# SCH_Pico_funboard_core2_2025-12-29.net
KiCad netlist of a schematic drawn in EasyEDA
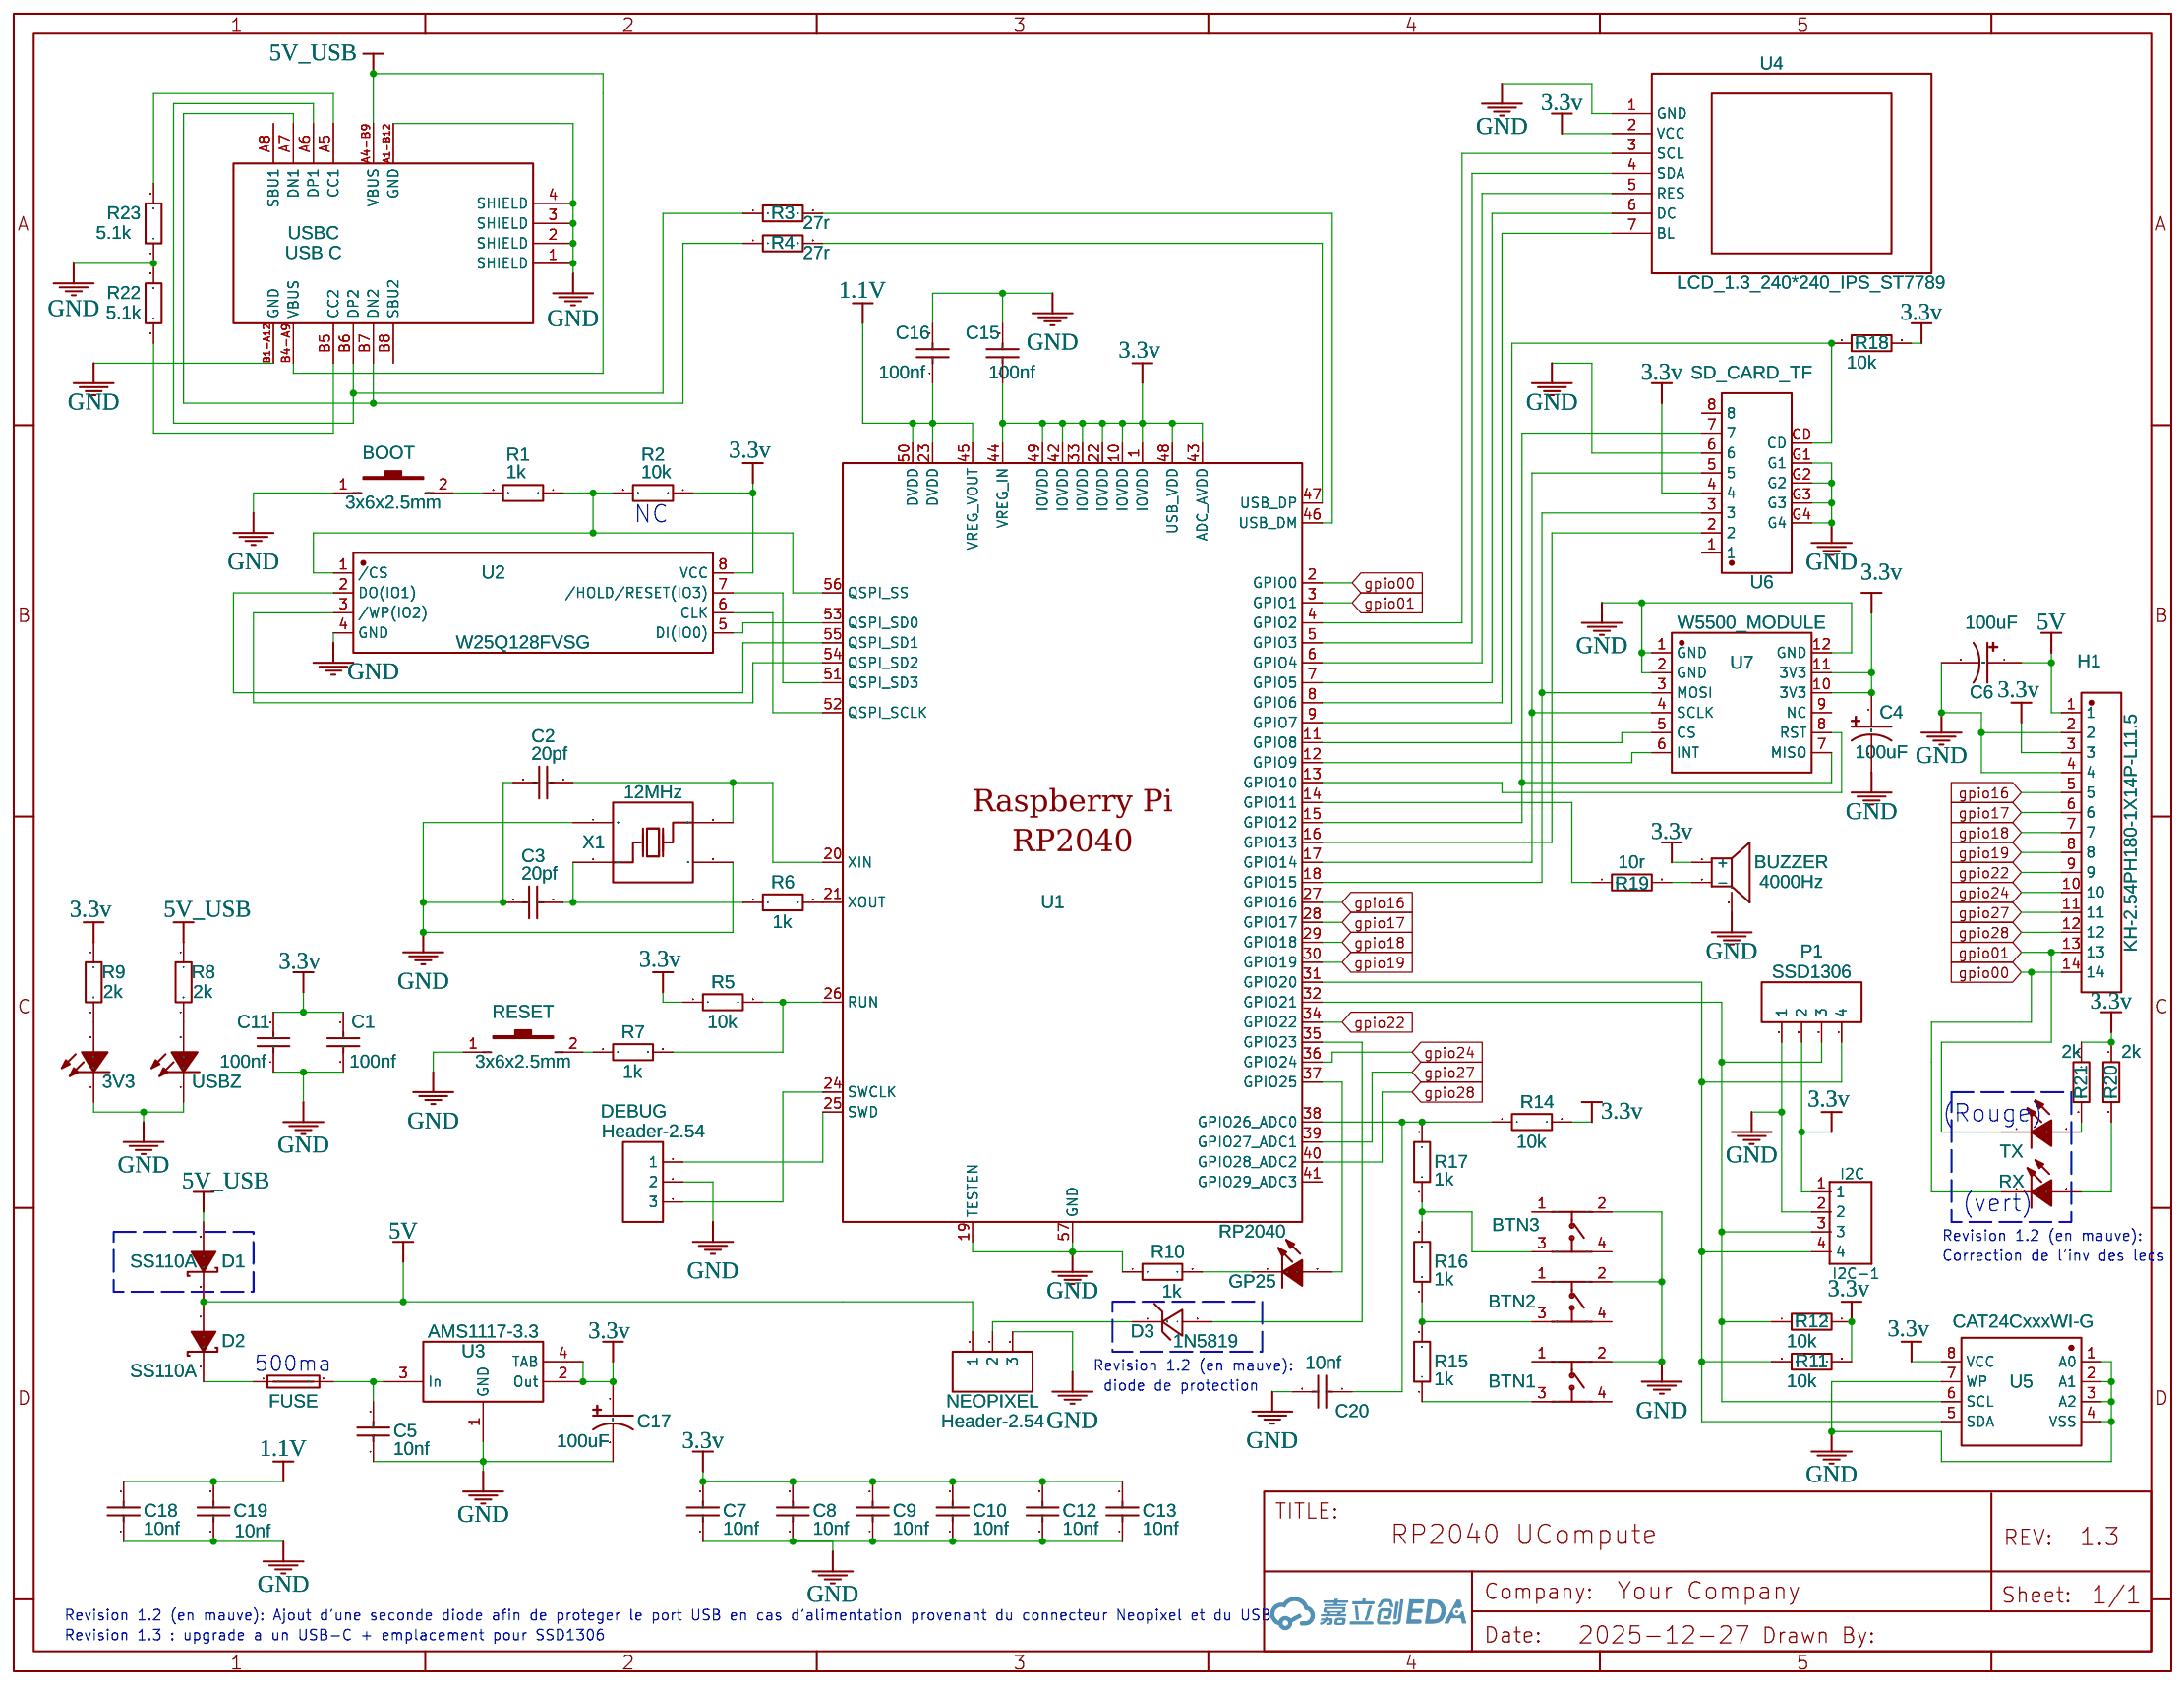
[diagram p0: schematic sheet]

(export (version "E")
  (design (tool "Eeschema 10.0.6"))
  (components
    (comp (ref "3V3")
      (value "XL-1206QPC")
      (fields (field (name "Manufacturer") "LCSC"))
      (libsource (lib "") (part "XL-1206QPC"))
    )
    (comp (ref "BOOT")
      (value "3x6x2.5mm")
      (fields (field (name "Manufacturer") "ReliaPro"))
      (libsource (lib "") (part "3x6x2.5mm"))
    )
    (comp (ref "BTN1")
      (value "TC-1102-A-J-R")
      (fields (field (name "Manufacturer") "XKB Connectivity(中国星坤)"))
      (libsource (lib "") (part "TC-1102-A-J-R"))
    )
    (comp (ref "BTN2")
      (value "TC-1102-A-J-R")
      (fields (field (name "Manufacturer") "XKB Connectivity(中国星坤)"))
      (libsource (lib "") (part "TC-1102-A-J-R"))
    )
    (comp (ref "BTN3")
      (value "TC-1102-A-J-R")
      (fields (field (name "Manufacturer") "XKB Connectivity(中国星坤)"))
      (libsource (lib "") (part "TC-1102-A-J-R"))
    )
    (comp (ref "BUZZER")
      (value "4000Hz")
      (fields (field (name "Manufacturer Part") "MLT-5030") (field (name "Manufacturer") "华能"))
      (libsource (lib "") (part "MLT-5030"))
    )
    (comp (ref "C1")
      (value "100nf")
      (fields (field (name "Manufacturer Part") "0805CG220J500NT") (field (name "Manufacturer") "FH"))
      (libsource (lib "") (part "0805CG220J500NT_3"))
    )
    (comp (ref "C2")
      (value "20pf")
      (fields (field (name "Manufacturer Part") "0805CG220J500NT") (field (name "Manufacturer") "FH"))
      (libsource (lib "") (part "0805CG220J500NT"))
    )
    (comp (ref "C3")
      (value "20pf")
      (fields (field (name "Manufacturer Part") "0805CG220J500NT") (field (name "Manufacturer") "FH"))
      (libsource (lib "") (part "0805CG220J500NT"))
    )
    (comp (ref "C4")
      (value "100uF")
      (fields
        (field (name "Manufacturer Part") "TLJA107M010R1400")
        (field (name "Manufacturer") "Kyocera AVX")
      )
      (libsource (lib "") (part "TLJA107M010R1400"))
    )
    (comp (ref "C5")
      (value "10nf")
      (fields (field (name "Manufacturer Part") "0805CG220J500NT") (field (name "Manufacturer") "FH"))
      (libsource (lib "") (part "0805CG220J500NT_1"))
    )
    (comp (ref "C6")
      (value "100uF")
      (fields
        (field (name "Manufacturer Part") "TLJA107M010R1400")
        (field (name "Manufacturer") "Kyocera AVX")
      )
      (libsource (lib "") (part "TLJA107M010R1400_1"))
    )
    (comp (ref "C7")
      (value "10nf")
      (fields (field (name "Manufacturer Part") "0805CG220J500NT") (field (name "Manufacturer") "FH"))
      (libsource (lib "") (part "0805CG220J500NT_1"))
    )
    (comp (ref "C8")
      (value "10nf")
      (fields (field (name "Manufacturer Part") "0805CG220J500NT") (field (name "Manufacturer") "FH"))
      (libsource (lib "") (part "0805CG220J500NT_1"))
    )
    (comp (ref "C9")
      (value "10nf")
      (fields (field (name "Manufacturer Part") "0805CG220J500NT") (field (name "Manufacturer") "FH"))
      (libsource (lib "") (part "0805CG220J500NT_1"))
    )
    (comp (ref "C10")
      (value "10nf")
      (fields (field (name "Manufacturer Part") "0805CG220J500NT") (field (name "Manufacturer") "FH"))
      (libsource (lib "") (part "0805CG220J500NT_1"))
    )
    (comp (ref "C11")
      (value "100nf")
      (fields (field (name "Manufacturer Part") "0805CG220J500NT") (field (name "Manufacturer") "FH"))
      (libsource (lib "") (part "0805CG220J500NT_1"))
    )
    (comp (ref "C12")
      (value "10nf")
      (fields (field (name "Manufacturer Part") "0805CG220J500NT") (field (name "Manufacturer") "FH"))
      (libsource (lib "") (part "0805CG220J500NT_1"))
    )
    (comp (ref "C13")
      (value "10nf")
      (fields (field (name "Manufacturer Part") "0805CG220J500NT") (field (name "Manufacturer") "FH"))
      (libsource (lib "") (part "0805CG220J500NT_1"))
    )
    (comp (ref "C15")
      (value "100nf")
      (fields (field (name "Manufacturer Part") "0805CG220J500NT") (field (name "Manufacturer") "FH"))
      (libsource (lib "") (part "0805CG220J500NT_1"))
    )
    (comp (ref "C16")
      (value "100nf")
      (fields (field (name "Manufacturer Part") "0805CG220J500NT") (field (name "Manufacturer") "FH"))
      (libsource (lib "") (part "0805CG220J500NT_1"))
    )
    (comp (ref "C17")
      (value "100uF")
      (fields
        (field (name "Manufacturer Part") "TLJA107M010R1400")
        (field (name "Manufacturer") "Kyocera AVX")
      )
      (libsource (lib "") (part "TLJA107M010R1400_2"))
    )
    (comp (ref "C18")
      (value "10nf")
      (fields (field (name "Manufacturer Part") "0805CG220J500NT") (field (name "Manufacturer") "FH"))
      (libsource (lib "") (part "0805CG220J500NT_1"))
    )
    (comp (ref "C19")
      (value "10nf")
      (fields (field (name "Manufacturer Part") "0805CG220J500NT") (field (name "Manufacturer") "FH"))
      (libsource (lib "") (part "0805CG220J500NT_1"))
    )
    (comp (ref "C20")
      (value "10nf")
      (fields (field (name "Manufacturer Part") "0805CG220J500NT") (field (name "Manufacturer") "FH"))
      (libsource (lib "") (part "0805CG220J500NT_2"))
    )
    (comp (ref "D1")
      (value "SS110A")
      (fields (field (name "Manufacturer") "Yangzhou Yangjie Elec Tech"))
      (libsource (lib "") (part "SS110A"))
    )
    (comp (ref "D2")
      (value "SS110A")
      (fields (field (name "Manufacturer") "Yangzhou Yangjie Elec Tech"))
      (libsource (lib "") (part "SS110A"))
    )
    (comp (ref "D3")
      (value "1N5819")
      (fields (field (name "Manufacturer Part") "1N4148D"))
      (libsource (lib "") (part "1N4148D"))
    )
    (comp (ref "DEBUG")
      (value "Header-2.54")
      (fields (field (name "Manufacturer Part") "2.54-1*3P针") (field (name "Manufacturer") "BOOMELE(博穆精密)"))
      (libsource (lib "") (part "Header-Male-2.54_1x3"))
    )
    (comp (ref "FUSE")
      (value "FUSE1206")
      (fields (field (name "Manufacturer Part") "D22051903536_fuse1206"))
      (libsource (lib "") (part "D22051903536_FUSE1206"))
    )
    (comp (ref "GP25")
      (value "XL-1206QPC")
      (fields (field (name "Manufacturer") "LCSC"))
      (libsource (lib "") (part "XL-1206QPC_4"))
    )
    (comp (ref "H1")
      (value "KH-2.54PH180-1X14P-L11.5")
      (fields (field (name "Manufacturer") "kinghelm(金航标)"))
      (libsource (lib "") (part "KH-2.54PH180-1X14P-L11.5"))
    )
    (comp (ref "I2C-1") (value "I2C") (libsource (lib "") (part "Unknown_921_-225")))
    (comp (ref "NEOPIXEL")
      (value "Header-2.54")
      (fields (field (name "Manufacturer Part") "2.54-1*3P针") (field (name "Manufacturer") "BOOMELE(博穆精密)"))
      (libsource (lib "") (part "Header-Male-2.54_1x3_1"))
    )
    (comp (ref "P1")
      (value "SSD1306")
      (fields
        (field (name "Manufacturer Part") "Header-Female-2.54_1x4")
        (field (name "Manufacturer") "ReliaPro")
      )
      (libsource (lib "") (part "Header-Female-2.54_1x4"))
    )
    (comp (ref "R1")
      (value "1k")
      (fields (field (name "Manufacturer Part") "RC0805DR-071KL") (field (name "Manufacturer") "YAGEO(国巨)"))
      (libsource (lib "") (part "RC0805DR-071KL_3"))
    )
    (comp (ref "R2")
      (value "10k")
      (fields (field (name "Manufacturer Part") "RC0805DR-071KL") (field (name "Manufacturer") "YAGEO(国巨)"))
      (libsource (lib "") (part "RC0805DR-071KL_3"))
    )
    (comp (ref "R3")
      (value "27r")
      (fields (field (name "Manufacturer Part") "RC0805DR-071KL") (field (name "Manufacturer") "YAGEO(国巨)"))
      (libsource (lib "") (part "RC0805DR-071KL"))
    )
    (comp (ref "R4")
      (value "27r")
      (fields (field (name "Manufacturer Part") "RC0805DR-071KL") (field (name "Manufacturer") "YAGEO(国巨)"))
      (libsource (lib "") (part "RC0805DR-071KL"))
    )
    (comp (ref "R5")
      (value "10k")
      (fields (field (name "Manufacturer Part") "RC0805DR-071KL") (field (name "Manufacturer") "YAGEO(国巨)"))
      (libsource (lib "") (part "RC0805DR-071KL"))
    )
    (comp (ref "R6")
      (value "1k")
      (fields (field (name "Manufacturer Part") "RC0805DR-071KL") (field (name "Manufacturer") "YAGEO(国巨)"))
      (libsource (lib "") (part "RC0805DR-071KL"))
    )
    (comp (ref "R7")
      (value "1k")
      (fields (field (name "Manufacturer Part") "RC0805DR-071KL") (field (name "Manufacturer") "YAGEO(国巨)"))
      (libsource (lib "") (part "RC0805DR-071KL"))
    )
    (comp (ref "R8")
      (value "2k")
      (fields (field (name "Manufacturer Part") "RC0805DR-071KL") (field (name "Manufacturer") "YAGEO(国巨)"))
      (libsource (lib "") (part "RC0805DR-071KL_1"))
    )
    (comp (ref "R9")
      (value "2k")
      (fields (field (name "Manufacturer Part") "RC0805DR-071KL") (field (name "Manufacturer") "YAGEO(国巨)"))
      (libsource (lib "") (part "RC0805DR-071KL_1"))
    )
    (comp (ref "R10")
      (value "1k")
      (fields (field (name "Manufacturer Part") "RC0805DR-071KL") (field (name "Manufacturer") "YAGEO(国巨)"))
      (libsource (lib "") (part "RC0805DR-071KL"))
    )
    (comp (ref "R11")
      (value "10k")
      (fields (field (name "Manufacturer Part") "RC0805DR-071KL") (field (name "Manufacturer") "YAGEO(国巨)"))
      (libsource (lib "") (part "RC0805DR-071KL"))
    )
    (comp (ref "R12")
      (value "10k")
      (fields (field (name "Manufacturer Part") "RC0805DR-071KL") (field (name "Manufacturer") "YAGEO(国巨)"))
      (libsource (lib "") (part "RC0805DR-071KL"))
    )
    (comp (ref "R14")
      (value "10k")
      (fields (field (name "Manufacturer Part") "RC0805DR-071KL") (field (name "Manufacturer") "YAGEO(国巨)"))
      (libsource (lib "") (part "RC0805DR-071KL"))
    )
    (comp (ref "R15")
      (value "1k")
      (fields (field (name "Manufacturer Part") "RC0805DR-071KL") (field (name "Manufacturer") "YAGEO(国巨)"))
      (libsource (lib "") (part "RC0805DR-071KL_2"))
    )
    (comp (ref "R16")
      (value "1k")
      (fields (field (name "Manufacturer Part") "RC0805DR-071KL") (field (name "Manufacturer") "YAGEO(国巨)"))
      (libsource (lib "") (part "RC0805DR-071KL_2"))
    )
    (comp (ref "R17")
      (value "1k")
      (fields (field (name "Manufacturer Part") "RC0805DR-071KL") (field (name "Manufacturer") "YAGEO(国巨)"))
      (libsource (lib "") (part "RC0805DR-071KL_2"))
    )
    (comp (ref "R18")
      (value "10k")
      (fields (field (name "Manufacturer Part") "RC0805DR-071KL") (field (name "Manufacturer") "YAGEO(国巨)"))
      (libsource (lib "") (part "RC0805DR-071KL"))
    )
    (comp (ref "R19")
      (value "10r")
      (fields (field (name "Manufacturer Part") "RC0805DR-071KL") (field (name "Manufacturer") "YAGEO(国巨)"))
      (libsource (lib "") (part "RC0805DR-071KL"))
    )
    (comp (ref "R20")
      (value "2k")
      (fields (field (name "Manufacturer Part") "RC0805DR-071KL") (field (name "Manufacturer") "YAGEO(国巨)"))
      (libsource (lib "") (part "RC0805DR-071KL_1"))
    )
    (comp (ref "R21")
      (value "2k")
      (fields (field (name "Manufacturer Part") "RC0805DR-071KL") (field (name "Manufacturer") "YAGEO(国巨)"))
      (libsource (lib "") (part "RC0805DR-071KL_1"))
    )
    (comp (ref "R22")
      (value "5.1k")
      (fields (field (name "Manufacturer Part") "RC0805DR-071KL") (field (name "Manufacturer") "YAGEO(国巨)"))
      (libsource (lib "") (part "RC0805DR-071KL_2"))
    )
    (comp (ref "R23")
      (value "5.1k")
      (fields (field (name "Manufacturer Part") "RC0805DR-071KL") (field (name "Manufacturer") "YAGEO(国巨)"))
      (libsource (lib "") (part "RC0805DR-071KL_2"))
    )
    (comp (ref "RESET")
      (value "3x6x2.5mm")
      (fields (field (name "Manufacturer") "ReliaPro"))
      (libsource (lib "") (part "3x6x2.5mm_1"))
    )
    (comp (ref "RX1")
      (value "RX")
      (fields (field (name "Manufacturer Part") "XL-1206QPC") (field (name "Manufacturer") "LCSC"))
      (libsource (lib "") (part "XL-1206QPC_2"))
    )
    (comp (ref "TX1")
      (value "TX")
      (fields (field (name "Manufacturer Part") "XL-1206QPC") (field (name "Manufacturer") "LCSC"))
      (libsource (lib "") (part "XL-1206QPC_1"))
    )
    (comp (ref "U1")
      (value "RP2040")
      (fields (field (name "Manufacturer") "Raspberry Pi(树莓派)"))
      (libsource (lib "") (part "RP2040"))
    )
    (comp (ref "U2") (value "W25Q128FVSG") (libsource (lib "") (part "W25Q128FVSG")))
    (comp (ref "U3")
      (value "AMS1117-3.3")
      (fields (field (name "Manufacturer Part") "AMS1117-5.0") (field (name "Manufacturer") "SK"))
      (libsource (lib "") (part "AMS1117-5.0_C165483"))
    )
    (comp (ref "U4")
      (value "LCD_1.3_240*240_IPS_ST7789")
      (libsource (lib "") (part "LCD_1.3_240*240_IPS_ST7789"))
    )
    (comp (ref "U5") (value "CAT24CxxxWI-G") (libsource (lib "") (part "CAT24C256WI-G")))
    (comp (ref "U6")
      (value "SD_CARD_TF")
      (fields (field (name "Manufacturer Part") "SD_Card_TF"))
      (libsource (lib "") (part "SD_CARD_TF"))
    )
    (comp (ref "U7") (value "W5500_MODULE") (libsource (lib "") (part "W5500_MODULE")))
    (comp (ref "USBC")
      (value "USB C")
      (fields (field (name "Manufacturer Part") "MC-311D") (field (name "Manufacturer") "SOFNG"))
      (libsource (lib "") (part "USB C"))
    )
    (comp (ref "USBZ")
      (value "XL-1206QPC")
      (fields (field (name "Manufacturer") "LCSC"))
      (libsource (lib "") (part "XL-1206QPC_3"))
    )
    (comp (ref "X1")
      (value "12MHz")
      (fields
        (field (name "Manufacturer Part") "TSX-3225 12MHz 20pF 30ppm")
        (field (name "Manufacturer") "EPSON")
      )
      (libsource (lib "") (part "TSX-3225 12MHz 20pF 30ppm"))
    )
  )
  (nets
    (net (code "1") (name "1.1V") (class "Default")
      (node (ref "C16") (pin "1") (pinfunction "1_1") (pintype "input"))
      (node (ref "C18") (pin "2") (pinfunction "2_2") (pintype "input"))
      (node (ref "C19") (pin "2") (pinfunction "2_2") (pintype "input"))
      (node (ref "U1") (pin "23") (pinfunction "DVDD_23") (pintype "bidirectional"))
      (node (ref "U1") (pin "45") (pinfunction "VREG_VOUT_45") (pintype "bidirectional"))
      (node (ref "U1") (pin "50") (pinfunction "DVDD_50") (pintype "bidirectional"))
    )
    (net (code "2") (name "3.3v") (class "Default")
      (node (ref "BUZZER") (pin "2") (pinfunction "+_2") (pintype "unspecified"))
      (node (ref "C1") (pin "1") (pinfunction "1_1") (pintype "input"))
      (node (ref "C10") (pin "2") (pinfunction "2_2") (pintype "input"))
      (node (ref "C11") (pin "2") (pinfunction "2_2") (pintype "input"))
      (node (ref "C12") (pin "2") (pinfunction "2_2") (pintype "input"))
      (node (ref "C13") (pin "2") (pinfunction "2_2") (pintype "input"))
      (node (ref "C15") (pin "1") (pinfunction "1_1") (pintype "input"))
      (node (ref "C17") (pin "1") (pinfunction "1_1") (pintype "unspecified"))
      (node (ref "C4") (pin "1") (pinfunction "1_1") (pintype "unspecified"))
      (node (ref "C7") (pin "2") (pinfunction "2_2") (pintype "input"))
      (node (ref "C8") (pin "2") (pinfunction "2_2") (pintype "input"))
      (node (ref "C9") (pin "2") (pinfunction "2_2") (pintype "input"))
      (node (ref "H1") (pin "3") (pinfunction "3_3") (pintype "unspecified"))
      (node (ref "I2C-1") (pin "1") (pinfunction "1_1") (pintype "bidirectional"))
      (node (ref "P1") (pin "2") (pinfunction "2_2") (pintype "input"))
      (node (ref "R11") (pin "2") (pinfunction "2_2") (pintype "unspecified"))
      (node (ref "R12") (pin "2") (pinfunction "2_2") (pintype "unspecified"))
      (node (ref "R14") (pin "2") (pinfunction "2_2") (pintype "unspecified"))
      (node (ref "R18") (pin "2") (pinfunction "2_2") (pintype "unspecified"))
      (node (ref "R2") (pin "1") (pinfunction "1_1") (pintype "unspecified"))
      (node (ref "R20") (pin "1") (pinfunction "1_1") (pintype "unspecified"))
      (node (ref "R21") (pin "1") (pinfunction "1_1") (pintype "unspecified"))
      (node (ref "R5") (pin "1") (pinfunction "1_1") (pintype "unspecified"))
      (node (ref "R9") (pin "1") (pinfunction "1_1") (pintype "unspecified"))
      (node (ref "U1") (pin "1") (pinfunction "IOVDD_1") (pintype "bidirectional"))
      (node (ref "U1") (pin "10") (pinfunction "IOVDD_10") (pintype "bidirectional"))
      (node (ref "U1") (pin "22") (pinfunction "IOVDD_22") (pintype "bidirectional"))
      (node (ref "U1") (pin "33") (pinfunction "IOVDD_33") (pintype "bidirectional"))
      (node (ref "U1") (pin "42") (pinfunction "IOVDD_42") (pintype "bidirectional"))
      (node (ref "U1") (pin "43") (pinfunction "ADC_AVDD_43") (pintype "bidirectional"))
      (node (ref "U1") (pin "44") (pinfunction "VREG_IN_44") (pintype "bidirectional"))
      (node (ref "U1") (pin "48") (pinfunction "USB_VDD_48") (pintype "bidirectional"))
      (node (ref "U1") (pin "49") (pinfunction "IOVDD_49") (pintype "bidirectional"))
      (node (ref "U2") (pin "8") (pinfunction "VCC_8") (pintype "unspecified"))
      (node (ref "U3") (pin "2") (pinfunction "Out_2") (pintype "unspecified"))
      (node (ref "U3") (pin "4") (pinfunction "TAB_4") (pintype "unspecified"))
      (node (ref "U4") (pin "2") (pinfunction "VCC_2") (pintype "unspecified"))
      (node (ref "U5") (pin "8") (pinfunction "VCC_8") (pintype "unspecified"))
      (node (ref "U6") (pin "4") (pinfunction "4_4") (pintype "unspecified"))
      (node (ref "U7") (pin "10") (pinfunction "3V3_10") (pintype "unspecified"))
      (node (ref "U7") (pin "11") (pinfunction "3V3_11") (pintype "unspecified"))
    )
    (net (code "3") (name "5V") (class "Default")
      (node (ref "C6") (pin "1") (pinfunction "1_1") (pintype "unspecified"))
      (node (ref "D1") (pin "2") (pinfunction "A_2") (pintype "unspecified"))
      (node (ref "D2") (pin "1") (pinfunction "K_1") (pintype "unspecified"))
      (node (ref "H1") (pin "1") (pinfunction "1_1") (pintype "unspecified"))
      (node (ref "NEOPIXEL") (pin "1") (pinfunction "1_1") (pintype "input"))
    )
    (net (code "4") (name "5V_USB") (class "Default")
      (node (ref "D2") (pin "2") (pinfunction "A_2") (pintype "unspecified"))
      (node (ref "R8") (pin "1") (pinfunction "1_1") (pintype "unspecified"))
      (node (ref "USBC") (pin "A4-B9") (pinfunction "VBUS_A4-B9") (pintype "unspecified"))
      (node (ref "USBC") (pin "B4-A9") (pinfunction "VBUS_B4-A9") (pintype "unspecified"))
    )
    (net (code "5") (name "GND") (class "Default")
      (node (ref "3V3") (pin "1") (pinfunction "K_1") (pintype "unspecified"))
      (node (ref "BOOT") (pin "1") (pinfunction "1_1") (pintype "input"))
      (node (ref "BTN1") (pin "2") (pinfunction "2_2") (pintype "unspecified"))
      (node (ref "BTN2") (pin "2") (pinfunction "2_2") (pintype "unspecified"))
      (node (ref "BTN3") (pin "2") (pinfunction "2_2") (pintype "unspecified"))
      (node (ref "BUZZER") (pin "1") (pinfunction "NC_1") (pintype "unspecified"))
      (node (ref "C1") (pin "2") (pinfunction "2_2") (pintype "input"))
      (node (ref "C10") (pin "1") (pinfunction "1_1") (pintype "input"))
      (node (ref "C11") (pin "1") (pinfunction "1_1") (pintype "input"))
      (node (ref "C12") (pin "1") (pinfunction "1_1") (pintype "input"))
      (node (ref "C13") (pin "1") (pinfunction "1_1") (pintype "input"))
      (node (ref "C15") (pin "2") (pinfunction "2_2") (pintype "input"))
      (node (ref "C16") (pin "2") (pinfunction "2_2") (pintype "input"))
      (node (ref "C17") (pin "2") (pinfunction "2_2") (pintype "unspecified"))
      (node (ref "C18") (pin "1") (pinfunction "1_1") (pintype "input"))
      (node (ref "C19") (pin "1") (pinfunction "1_1") (pintype "input"))
      (node (ref "C2") (pin "1") (pinfunction "1_1") (pintype "input"))
      (node (ref "C20") (pin "2") (pinfunction "2_2") (pintype "input"))
      (node (ref "C3") (pin "1") (pinfunction "1_1") (pintype "input"))
      (node (ref "C4") (pin "2") (pinfunction "2_2") (pintype "unspecified"))
      (node (ref "C5") (pin "1") (pinfunction "1_1") (pintype "input"))
      (node (ref "C6") (pin "2") (pinfunction "2_2") (pintype "unspecified"))
      (node (ref "C7") (pin "1") (pinfunction "1_1") (pintype "input"))
      (node (ref "C8") (pin "1") (pinfunction "1_1") (pintype "input"))
      (node (ref "C9") (pin "1") (pinfunction "1_1") (pintype "input"))
      (node (ref "DEBUG") (pin "2") (pinfunction "2_2") (pintype "input"))
      (node (ref "H1") (pin "2") (pinfunction "2_2") (pintype "unspecified"))
      (node (ref "H1") (pin "4") (pinfunction "4_4") (pintype "unspecified"))
      (node (ref "I2C-1") (pin "2") (pinfunction "2_2") (pintype "bidirectional"))
      (node (ref "NEOPIXEL") (pin "3") (pinfunction "3_3") (pintype "input"))
      (node (ref "P1") (pin "1") (pinfunction "1_1") (pintype "input"))
      (node (ref "R10") (pin "1") (pinfunction "1_1") (pintype "unspecified"))
      (node (ref "R22") (pin "2") (pinfunction "2_2") (pintype "unspecified"))
      (node (ref "R23") (pin "1") (pinfunction "1_1") (pintype "unspecified"))
      (node (ref "RESET") (pin "1") (pinfunction "1_1") (pintype "input"))
      (node (ref "U1") (pin "19") (pinfunction "TESTEN_19") (pintype "unspecified"))
      (node (ref "U1") (pin "57") (pinfunction "GND_57") (pintype "bidirectional"))
      (node (ref "U2") (pin "4") (pinfunction "GND_4") (pintype "unspecified"))
      (node (ref "U3") (pin "1") (pinfunction "GND_1") (pintype "unspecified"))
      (node (ref "U4") (pin "1") (pinfunction "GND_1") (pintype "unspecified"))
      (node (ref "U5") (pin "1") (pinfunction "A0_1") (pintype "unspecified"))
      (node (ref "U5") (pin "2") (pinfunction "A1_2") (pintype "unspecified"))
      (node (ref "U5") (pin "3") (pinfunction "A2_3") (pintype "unspecified"))
      (node (ref "U5") (pin "4") (pinfunction "VSS_4") (pintype "unspecified"))
      (node (ref "U5") (pin "7") (pinfunction "WP_7") (pintype "unspecified"))
      (node (ref "U6") (pin "6") (pinfunction "6_6") (pintype "unspecified"))
      (node (ref "U6") (pin "G1") (pinfunction "G1_G1") (pintype "unspecified"))
      (node (ref "U6") (pin "G2") (pinfunction "G2_G2") (pintype "unspecified"))
      (node (ref "U6") (pin "G3") (pinfunction "G3_G3") (pintype "unspecified"))
      (node (ref "U6") (pin "G4") (pinfunction "G4_G4") (pintype "unspecified"))
      (node (ref "U7") (pin "1") (pinfunction "GND_1") (pintype "unspecified"))
      (node (ref "U7") (pin "12") (pinfunction "GND_12") (pintype "unspecified"))
      (node (ref "U7") (pin "2") (pinfunction "GND_2") (pintype "unspecified"))
      (node (ref "USBC") (pin "1") (pinfunction "SHIELD_1") (pintype "unspecified"))
      (node (ref "USBC") (pin "2") (pinfunction "SHIELD_2") (pintype "unspecified"))
      (node (ref "USBC") (pin "3") (pinfunction "SHIELD_3") (pintype "unspecified"))
      (node (ref "USBC") (pin "4") (pinfunction "SHIELD_4") (pintype "unspecified"))
      (node (ref "USBC") (pin "A1-B12") (pinfunction "GND_A1-B12") (pintype "unspecified"))
      (node (ref "USBC") (pin "B1-A12") (pinfunction "GND_B1-A12") (pintype "unspecified"))
      (node (ref "USBZ") (pin "1") (pinfunction "K_1") (pintype "unspecified"))
      (node (ref "X1") (pin "2") (pinfunction "NC_2") (pintype "input"))
      (node (ref "X1") (pin "4") (pinfunction "NC_4") (pintype "input"))
    )
    (net (code "6") (name "Net-(3V3-A)") (class "Default")
      (node (ref "3V3") (pin "2") (pinfunction "A_2") (pintype "unspecified"))
      (node (ref "R9") (pin "2") (pinfunction "2_2") (pintype "unspecified"))
    )
    (net (code "7") (name "Net-(BOOT-Pad2)") (class "Default")
      (node (ref "BOOT") (pin "2") (pinfunction "2_2") (pintype "input"))
      (node (ref "R1") (pin "2") (pinfunction "2_2") (pintype "unspecified"))
    )
    (net (code "8") (name "Net-(BTN1-Pad3)") (class "Default")
      (node (ref "BTN1") (pin "3") (pinfunction "3_3") (pintype "unspecified"))
      (node (ref "R15") (pin "1") (pinfunction "1_1") (pintype "unspecified"))
    )
    (net (code "9") (name "Net-(BTN2-Pad3)") (class "Default")
      (node (ref "BTN2") (pin "3") (pinfunction "3_3") (pintype "unspecified"))
      (node (ref "R15") (pin "2") (pinfunction "2_2") (pintype "unspecified"))
      (node (ref "R16") (pin "1") (pinfunction "1_1") (pintype "unspecified"))
    )
    (net (code "10") (name "Net-(BTN3-Pad3)") (class "Default")
      (node (ref "BTN3") (pin "3") (pinfunction "3_3") (pintype "unspecified"))
      (node (ref "R16") (pin "2") (pinfunction "2_2") (pintype "unspecified"))
      (node (ref "R17") (pin "1") (pinfunction "1_1") (pintype "unspecified"))
    )
    (net (code "11") (name "Net-(BUZZER--)") (class "Default")
      (node (ref "BUZZER") (pin "3") (pinfunction "-_3") (pintype "unspecified"))
      (node (ref "R19") (pin "2") (pinfunction "2_2") (pintype "unspecified"))
    )
    (net (code "12") (name "Net-(D1-K)") (class "Default")
      (node (ref "D1") (pin "1") (pinfunction "K_1") (pintype "unspecified"))
      (node (ref "FUSE") (pin "1") (pinfunction "1_1") (pintype "unspecified"))
    )
    (net (code "13") (name "Net-(D3-A)") (class "Default")
      (node (ref "D3") (pin "2") (pinfunction "A_2") (pintype "unspecified"))
      (node (ref "U1") (pin "35") (pinfunction "GPIO23_35") (pintype "bidirectional"))
    )
    (net (code "14") (name "Net-(D3-C)") (class "Default")
      (node (ref "D3") (pin "1") (pinfunction "C_1") (pintype "unspecified"))
      (node (ref "NEOPIXEL") (pin "2") (pinfunction "2_2") (pintype "input"))
    )
    (net (code "15") (name "Net-(GP25-A)") (class "Default")
      (node (ref "GP25") (pin "2") (pinfunction "A_2") (pintype "unspecified"))
      (node (ref "U1") (pin "37") (pinfunction "GPIO25_37") (pintype "bidirectional"))
    )
    (net (code "16") (name "Net-(GP25-K)") (class "Default")
      (node (ref "GP25") (pin "1") (pinfunction "K_1") (pintype "unspecified"))
      (node (ref "R10") (pin "2") (pinfunction "2_2") (pintype "unspecified"))
    )
    (net (code "17") (name "Net-(R7-Pad1)") (class "Default")
      (node (ref "R7") (pin "1") (pinfunction "1_1") (pintype "unspecified"))
      (node (ref "RESET") (pin "2") (pinfunction "2_2") (pintype "input"))
    )
    (net (code "18") (name "Net-(RX1-A)") (class "Default")
      (node (ref "R20") (pin "2") (pinfunction "2_2") (pintype "unspecified"))
      (node (ref "RX1") (pin "2") (pinfunction "A_2") (pintype "unspecified"))
    )
    (net (code "19") (name "Net-(TX1-A)") (class "Default")
      (node (ref "R21") (pin "2") (pinfunction "2_2") (pintype "unspecified"))
      (node (ref "TX1") (pin "2") (pinfunction "A_2") (pintype "unspecified"))
    )
    (net (code "20") (name "Net-(U1-GPIO2)") (class "Default")
      (node (ref "U1") (pin "4") (pinfunction "GPIO2_4") (pintype "bidirectional"))
      (node (ref "U4") (pin "3") (pinfunction "SCL_3") (pintype "unspecified"))
    )
    (net (code "21") (name "Net-(U1-GPIO3)") (class "Default")
      (node (ref "U1") (pin "5") (pinfunction "GPIO3_5") (pintype "bidirectional"))
      (node (ref "U4") (pin "4") (pinfunction "SDA_4") (pintype "unspecified"))
    )
    (net (code "22") (name "Net-(U1-GPIO4)") (class "Default")
      (node (ref "U1") (pin "6") (pinfunction "GPIO4_6") (pintype "bidirectional"))
      (node (ref "U4") (pin "5") (pinfunction "RES_5") (pintype "unspecified"))
    )
    (net (code "23") (name "Net-(U1-GPIO5)") (class "Default")
      (node (ref "U1") (pin "7") (pinfunction "GPIO5_7") (pintype "bidirectional"))
      (node (ref "U4") (pin "6") (pinfunction "DC_6") (pintype "unspecified"))
    )
    (net (code "24") (name "Net-(U1-GPIO6)") (class "Default")
      (node (ref "U1") (pin "8") (pinfunction "GPIO6_8") (pintype "bidirectional"))
      (node (ref "U4") (pin "7") (pinfunction "BL_7") (pintype "unspecified"))
    )
    (net (code "25") (name "Net-(U1-GPIO7)") (class "Default")
      (node (ref "R18") (pin "1") (pinfunction "1_1") (pintype "unspecified"))
      (node (ref "U1") (pin "9") (pinfunction "GPIO7_9") (pintype "bidirectional"))
      (node (ref "U6") (pin "CD") (pinfunction "CD_CD") (pintype "unspecified"))
    )
    (net (code "26") (name "Net-(U1-GPIO8)") (class "Default")
      (node (ref "U1") (pin "11") (pinfunction "GPIO8_11") (pintype "bidirectional"))
      (node (ref "U7") (pin "5") (pinfunction "CS_5") (pintype "unspecified"))
    )
    (net (code "27") (name "Net-(U1-GPIO9)") (class "Default")
      (node (ref "U1") (pin "12") (pinfunction "GPIO9_12") (pintype "bidirectional"))
      (node (ref "U7") (pin "6") (pinfunction "INT_6") (pintype "unspecified"))
    )
    (net (code "28") (name "Net-(U1-GPIO10)") (class "Default")
      (node (ref "U1") (pin "13") (pinfunction "GPIO10_13") (pintype "bidirectional"))
      (node (ref "U7") (pin "8") (pinfunction "RST_8") (pintype "unspecified"))
    )
    (net (code "29") (name "Net-(U1-GPIO11)") (class "Default")
      (node (ref "R19") (pin "1") (pinfunction "1_1") (pintype "unspecified"))
      (node (ref "U1") (pin "14") (pinfunction "GPIO11_14") (pintype "bidirectional"))
    )
    (net (code "30") (name "Net-(U1-GPIO12)") (class "Default")
      (node (ref "U1") (pin "15") (pinfunction "GPIO12_15") (pintype "bidirectional"))
      (node (ref "U6") (pin "7") (pinfunction "7_7") (pintype "unspecified"))
      (node (ref "U7") (pin "7") (pinfunction "MISO_7") (pintype "unspecified"))
    )
    (net (code "31") (name "Net-(U1-GPIO13)") (class "Default")
      (node (ref "U1") (pin "16") (pinfunction "GPIO13_16") (pintype "bidirectional"))
      (node (ref "U6") (pin "2") (pinfunction "2_2") (pintype "unspecified"))
    )
    (net (code "32") (name "Net-(U1-GPIO14)") (class "Default")
      (node (ref "U1") (pin "17") (pinfunction "GPIO14_17") (pintype "bidirectional"))
      (node (ref "U6") (pin "5") (pinfunction "5_5") (pintype "unspecified"))
      (node (ref "U7") (pin "4") (pinfunction "SCLK_4") (pintype "unspecified"))
    )
    (net (code "33") (name "Net-(U1-GPIO15)") (class "Default")
      (node (ref "U1") (pin "18") (pinfunction "GPIO15_18") (pintype "bidirectional"))
      (node (ref "U6") (pin "3") (pinfunction "3_3") (pintype "unspecified"))
      (node (ref "U7") (pin "3") (pinfunction "MOSI_3") (pintype "unspecified"))
    )
    (net (code "34") (name "Net-(U1-GPIO20)") (class "Default")
      (node (ref "I2C-1") (pin "4") (pinfunction "4_4") (pintype "bidirectional"))
      (node (ref "P1") (pin "4") (pinfunction "4_4") (pintype "input"))
      (node (ref "R11") (pin "1") (pinfunction "1_1") (pintype "unspecified"))
      (node (ref "U1") (pin "31") (pinfunction "GPIO20_31") (pintype "bidirectional"))
      (node (ref "U5") (pin "5") (pinfunction "SDA_5") (pintype "unspecified"))
    )
    (net (code "35") (name "Net-(U1-GPIO21)") (class "Default")
      (node (ref "I2C-1") (pin "3") (pinfunction "3_3") (pintype "bidirectional"))
      (node (ref "P1") (pin "3") (pinfunction "3_3") (pintype "input"))
      (node (ref "R12") (pin "1") (pinfunction "1_1") (pintype "unspecified"))
      (node (ref "U1") (pin "32") (pinfunction "GPIO21_32") (pintype "bidirectional"))
      (node (ref "U5") (pin "6") (pinfunction "SCL_6") (pintype "unspecified"))
    )
    (net (code "36") (name "Net-(U1-GPIO26_ADC0)") (class "Default")
      (node (ref "C20") (pin "1") (pinfunction "1_1") (pintype "input"))
      (node (ref "R14") (pin "1") (pinfunction "1_1") (pintype "unspecified"))
      (node (ref "R17") (pin "2") (pinfunction "2_2") (pintype "unspecified"))
      (node (ref "U1") (pin "38") (pinfunction "GPIO26_ADC0_38") (pintype "bidirectional"))
    )
    (net (code "37") (name "Net-(U1-QSPI_SCLK)") (class "Default")
      (node (ref "U1") (pin "52") (pinfunction "QSPI_SCLK_52") (pintype "output"))
      (node (ref "U2") (pin "6") (pinfunction "CLK_6") (pintype "unspecified"))
    )
    (net (code "38") (name "Net-(U1-QSPI_SD0)") (class "Default")
      (node (ref "U1") (pin "53") (pinfunction "QSPI_SD0_53") (pintype "bidirectional"))
      (node (ref "U2") (pin "5") (pinfunction "DI(IO0)_5") (pintype "unspecified"))
    )
    (net (code "39") (name "Net-(U1-QSPI_SD1)") (class "Default")
      (node (ref "U1") (pin "55") (pinfunction "QSPI_SD1_55") (pintype "bidirectional"))
      (node (ref "U2") (pin "2") (pinfunction "DO(IO1)_2") (pintype "unspecified"))
    )
    (net (code "40") (name "Net-(U1-QSPI_SD2)") (class "Default")
      (node (ref "U1") (pin "54") (pinfunction "QSPI_SD2_54") (pintype "bidirectional"))
      (node (ref "U2") (pin "3") (pinfunction "/WP(IO2)_3") (pintype "unspecified"))
    )
    (net (code "41") (name "Net-(U1-QSPI_SD3)") (class "Default")
      (node (ref "U1") (pin "51") (pinfunction "QSPI_SD3_51") (pintype "bidirectional"))
      (node (ref "U2") (pin "7") (pinfunction "/HOLD/RESET(IO3)_7") (pintype "unspecified"))
    )
    (net (code "42") (name "Net-(U1-QSPI_SS)") (class "Default")
      (node (ref "R1") (pin "1") (pinfunction "1_1") (pintype "unspecified"))
      (node (ref "R2") (pin "2") (pinfunction "2_2") (pintype "unspecified"))
      (node (ref "U1") (pin "56") (pinfunction "QSPI_SS_56") (pintype "bidirectional"))
      (node (ref "U2") (pin "1") (pinfunction "/CS_1") (pintype "unspecified"))
    )
    (net (code "43") (name "Net-(U1-RUN)") (class "Default")
      (node (ref "R5") (pin "2") (pinfunction "2_2") (pintype "unspecified"))
      (node (ref "R7") (pin "2") (pinfunction "2_2") (pintype "unspecified"))
      (node (ref "U1") (pin "26") (pinfunction "RUN_26") (pintype "input"))
    )
    (net (code "44") (name "Net-(U1-SWCLK)") (class "Default")
      (node (ref "DEBUG") (pin "3") (pinfunction "3_3") (pintype "input"))
      (node (ref "U1") (pin "24") (pinfunction "SWCLK_24") (pintype "output"))
    )
    (net (code "45") (name "Net-(U1-SWD)") (class "Default")
      (node (ref "DEBUG") (pin "1") (pinfunction "1_1") (pintype "input"))
      (node (ref "U1") (pin "25") (pinfunction "SWD_25") (pintype "bidirectional"))
    )
    (net (code "46") (name "Net-(U1-USB_DM)") (class "Default")
      (node (ref "R3") (pin "2") (pinfunction "2_2") (pintype "unspecified"))
      (node (ref "U1") (pin "46") (pinfunction "USB_DM_46") (pintype "bidirectional"))
    )
    (net (code "47") (name "Net-(U1-USB_DP)") (class "Default")
      (node (ref "R4") (pin "2") (pinfunction "2_2") (pintype "unspecified"))
      (node (ref "U1") (pin "47") (pinfunction "USB_DP_47") (pintype "bidirectional"))
    )
    (net (code "48") (name "Net-(U1-XIN)") (class "Default")
      (node (ref "C2") (pin "2") (pinfunction "2_2") (pintype "input"))
      (node (ref "U1") (pin "20") (pinfunction "XIN_20") (pintype "input"))
      (node (ref "X1") (pin "3") (pinfunction "OSC2_3") (pintype "input"))
    )
    (net (code "49") (name "Net-(U1-XOUT)") (class "Default")
      (node (ref "R6") (pin "2") (pinfunction "2_2") (pintype "unspecified"))
      (node (ref "U1") (pin "21") (pinfunction "XOUT_21") (pintype "unspecified"))
    )
    (net (code "50") (name "Net-(U3-In)") (class "Default")
      (node (ref "C5") (pin "2") (pinfunction "2_2") (pintype "input"))
      (node (ref "FUSE") (pin "2") (pinfunction "2_2") (pintype "unspecified"))
      (node (ref "U3") (pin "3") (pinfunction "In_3") (pintype "unspecified"))
    )
    (net (code "51") (name "Net-(USBC-CC1)") (class "Default")
      (node (ref "R23") (pin "2") (pinfunction "2_2") (pintype "unspecified"))
      (node (ref "USBC") (pin "A5") (pinfunction "CC1_A5") (pintype "unspecified"))
    )
    (net (code "52") (name "Net-(USBC-CC2)") (class "Default")
      (node (ref "R22") (pin "1") (pinfunction "1_1") (pintype "unspecified"))
      (node (ref "USBC") (pin "B5") (pinfunction "CC2_B5") (pintype "unspecified"))
    )
    (net (code "53") (name "Net-(USBC-DN1)") (class "Default")
      (node (ref "R4") (pin "1") (pinfunction "1_1") (pintype "unspecified"))
      (node (ref "USBC") (pin "A7") (pinfunction "DN1_A7") (pintype "unspecified"))
      (node (ref "USBC") (pin "B7") (pinfunction "DN2_B7") (pintype "unspecified"))
    )
    (net (code "54") (name "Net-(USBC-DP1)") (class "Default")
      (node (ref "R3") (pin "1") (pinfunction "1_1") (pintype "unspecified"))
      (node (ref "USBC") (pin "A6") (pinfunction "DP1_A6") (pintype "unspecified"))
      (node (ref "USBC") (pin "B6") (pinfunction "DP2_B6") (pintype "unspecified"))
    )
    (net (code "55") (name "Net-(USBZ-A)") (class "Default")
      (node (ref "R8") (pin "2") (pinfunction "2_2") (pintype "unspecified"))
      (node (ref "USBZ") (pin "2") (pinfunction "A_2") (pintype "unspecified"))
    )
    (net (code "56") (name "Net-(X1-OSC1)") (class "Default")
      (node (ref "C3") (pin "2") (pinfunction "2_2") (pintype "input"))
      (node (ref "R6") (pin "1") (pinfunction "1_1") (pintype "unspecified"))
      (node (ref "X1") (pin "1") (pinfunction "OSC1_1") (pintype "input"))
    )
    (net (code "57") (name "gpio00") (class "Default")
      (node (ref "H1") (pin "14") (pinfunction "14_14") (pintype "unspecified"))
      (node (ref "RX1") (pin "1") (pinfunction "K_1") (pintype "unspecified"))
      (node (ref "U1") (pin "2") (pinfunction "GPIO0_2") (pintype "bidirectional"))
    )
    (net (code "58") (name "gpio01") (class "Default")
      (node (ref "H1") (pin "13") (pinfunction "13_13") (pintype "unspecified"))
      (node (ref "TX1") (pin "1") (pinfunction "K_1") (pintype "unspecified"))
      (node (ref "U1") (pin "3") (pinfunction "GPIO1_3") (pintype "bidirectional"))
    )
    (net (code "59") (name "gpio16") (class "Default")
      (node (ref "H1") (pin "5") (pinfunction "5_5") (pintype "unspecified"))
      (node (ref "U1") (pin "27") (pinfunction "GPIO16_27") (pintype "bidirectional"))
    )
    (net (code "60") (name "gpio17") (class "Default")
      (node (ref "H1") (pin "6") (pinfunction "6_6") (pintype "unspecified"))
      (node (ref "U1") (pin "28") (pinfunction "GPIO17_28") (pintype "bidirectional"))
    )
    (net (code "61") (name "gpio18") (class "Default")
      (node (ref "H1") (pin "7") (pinfunction "7_7") (pintype "unspecified"))
      (node (ref "U1") (pin "29") (pinfunction "GPIO18_29") (pintype "bidirectional"))
    )
    (net (code "62") (name "gpio19") (class "Default")
      (node (ref "H1") (pin "8") (pinfunction "8_8") (pintype "unspecified"))
      (node (ref "U1") (pin "30") (pinfunction "GPIO19_30") (pintype "bidirectional"))
    )
    (net (code "63") (name "gpio22") (class "Default")
      (node (ref "H1") (pin "9") (pinfunction "9_9") (pintype "unspecified"))
      (node (ref "U1") (pin "34") (pinfunction "GPIO22_34") (pintype "bidirectional"))
    )
    (net (code "64") (name "gpio24") (class "Default")
      (node (ref "H1") (pin "10") (pinfunction "10_10") (pintype "unspecified"))
      (node (ref "U1") (pin "36") (pinfunction "GPIO24_36") (pintype "bidirectional"))
    )
    (net (code "65") (name "gpio27") (class "Default")
      (node (ref "H1") (pin "11") (pinfunction "11_11") (pintype "unspecified"))
      (node (ref "U1") (pin "39") (pinfunction "GPIO27_ADC1_39") (pintype "bidirectional"))
    )
    (net (code "66") (name "gpio28") (class "Default")
      (node (ref "H1") (pin "12") (pinfunction "12_12") (pintype "unspecified"))
      (node (ref "U1") (pin "40") (pinfunction "GPIO28_ADC2_40") (pintype "bidirectional"))
    )
    (net (code "67") (name "unconnected-(BTN1-Pad1)") (class "Default")
      (node (ref "BTN1") (pin "1") (pinfunction "1_1") (pintype "unspecified"))
    )
    (net (code "68") (name "unconnected-(BTN1-Pad4)") (class "Default")
      (node (ref "BTN1") (pin "4") (pinfunction "4_4") (pintype "unspecified"))
    )
    (net (code "69") (name "unconnected-(BTN2-Pad1)") (class "Default")
      (node (ref "BTN2") (pin "1") (pinfunction "1_1") (pintype "unspecified"))
    )
    (net (code "70") (name "unconnected-(BTN2-Pad4)") (class "Default")
      (node (ref "BTN2") (pin "4") (pinfunction "4_4") (pintype "unspecified"))
    )
    (net (code "71") (name "unconnected-(BTN3-Pad1)") (class "Default")
      (node (ref "BTN3") (pin "1") (pinfunction "1_1") (pintype "unspecified"))
    )
    (net (code "72") (name "unconnected-(BTN3-Pad4)") (class "Default")
      (node (ref "BTN3") (pin "4") (pinfunction "4_4") (pintype "unspecified"))
    )
    (net (code "73") (name "unconnected-(U1-GPIO29_ADC3-Pad41)") (class "Default")
      (node (ref "U1") (pin "41") (pinfunction "GPIO29_ADC3_41") (pintype "bidirectional"))
    )
    (net (code "74") (name "unconnected-(U6-Pad1)") (class "Default")
      (node (ref "U6") (pin "1") (pinfunction "1_1") (pintype "unspecified"))
    )
    (net (code "75") (name "unconnected-(U6-Pad8)") (class "Default")
      (node (ref "U6") (pin "8") (pinfunction "8_8") (pintype "unspecified"))
    )
    (net (code "76") (name "unconnected-(U7-NC-Pad9)") (class "Default")
      (node (ref "U7") (pin "9") (pinfunction "NC_9") (pintype "unspecified"))
    )
    (net (code "77") (name "unconnected-(USBC-SBU1-PadA8)") (class "Default")
      (node (ref "USBC") (pin "A8") (pinfunction "SBU1_A8") (pintype "unspecified"))
    )
    (net (code "78") (name "unconnected-(USBC-SBU2-PadB8)") (class "Default")
      (node (ref "USBC") (pin "B8") (pinfunction "SBU2_B8") (pintype "unspecified"))
    )
  )
)
